# P-MT3620RDB-1-6_WiFi.net
KiCad netlist of a schematic drawn in Altium Designer
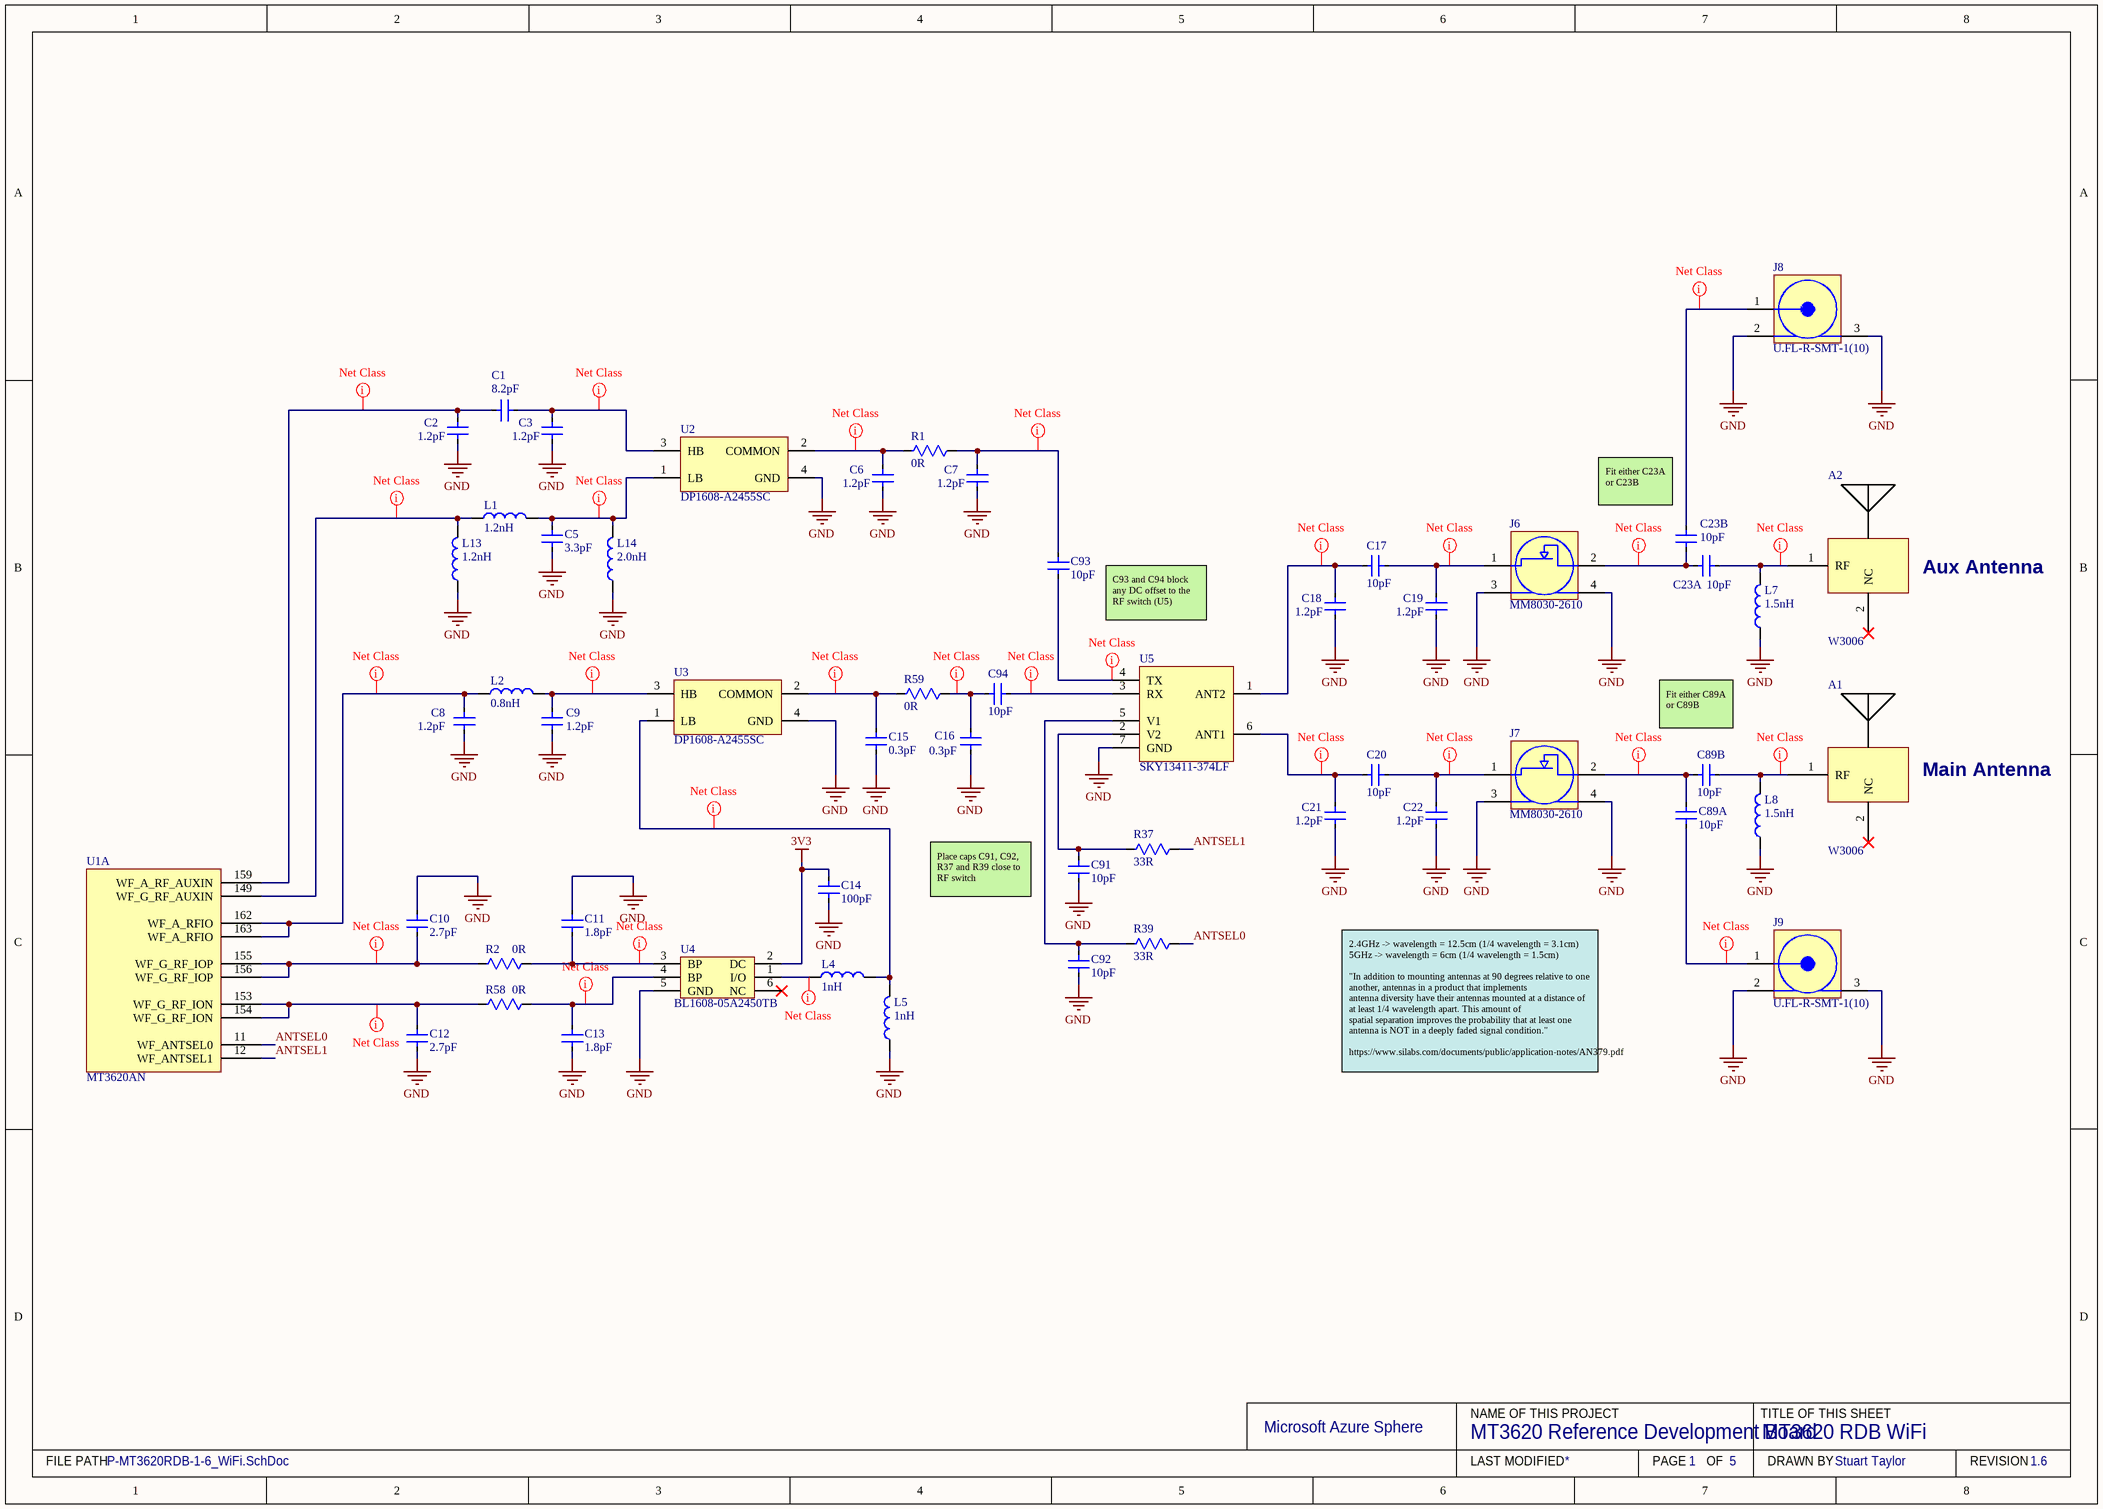
[diagram p0: P-MT3620RDB-1-6_WiFi.SchDoc]

(export (version "E")
  (design (tool "Eeschema 10.0.6"))
  (components
    (comp (ref "A1")
      (value "W3006")
      (footprint "W3006")
      (description "W3006 Chip Antenna")
      (fields (field (name "MANUFACTURER") "Pulse Electronics Corporation"))
      (libsource (lib "Pulse_W3006") (part "W3006"))
    )
    (comp (ref "A2")
      (value "W3006")
      (footprint "W3006")
      (description "W3006 Chip Antenna")
      (fields (field (name "MANUFACTURER") "Pulse Electronics Corporation"))
      (libsource (lib "Pulse_W3006") (part "W3006"))
    )
    (comp (ref "C1")
      (value "8.2pF")
      (footprint "TDK 2010")
      (description "CAP CER 8.2PF 25V NP0 0201")
      (fields
        (field (name "MANUFACTURER") "Murata")
        (field (name "MANUFACTURER PART NUMBER") "GJM0335C1E8R2CB01D")
      )
      (libsource (lib "Murata") (part "GJM0335C1E8R2CB01D"))
    )
    (comp (ref "C2")
      (value "1.2pF")
      (footprint "TDK 2010")
      (description "CAP CER 1.2PF 25V C0G 0201")
      (fields
        (field (name "MANUFACTURER") "TDK Corporation")
        (field (name "MANUFACTURER PART NUMBER") "C0603C0G1E1R2B")
      )
      (libsource (lib "TDK_Capacitor_C_0201") (part "1.2pF 0201 25V"))
    )
    (comp (ref "C3")
      (value "1.2pF")
      (footprint "TDK 2010")
      (description "CAP CER 1.2PF 25V C0G 0201")
      (fields
        (field (name "MANUFACTURER") "TDK Corporation")
        (field (name "MANUFACTURER PART NUMBER") "C0603C0G1E1R2B")
      )
      (libsource (lib "TDK_Capacitor_C_0201") (part "1.2pF 0201 25V"))
    )
    (comp (ref "C5")
      (value "3.3pF")
      (footprint "TDK 2010")
      (description "Cap Ceramic 3.3pF 25V C0G 0.25pF SMD 0201 125C T/R")
      (fields
        (field (name "MANUFACTURER") "TDK")
        (field (name "MANUFACTURER PART NUMBER") "CGA1A2C0G1E3R3C030BA")
      )
      (libsource (lib "TDK_Capacitor_C_0201") (part "3.3pF 0201 25V"))
    )
    (comp (ref "C6")
      (value "1.2pF")
      (footprint "TDK 2010")
      (description "CAP CER 1.2PF 25V C0G 0201")
      (fields
        (field (name "MANUFACTURER") "TDK Corporation")
        (field (name "MANUFACTURER PART NUMBER") "C0603C0G1E1R2B")
      )
      (libsource (lib "TDK_Capacitor_C_0201") (part "1.2pF 0201 25V"))
    )
    (comp (ref "C7")
      (value "1.2pF")
      (footprint "TDK 2010")
      (description "CAP CER 1.2PF 25V C0G 0201")
      (fields
        (field (name "MANUFACTURER") "TDK Corporation")
        (field (name "MANUFACTURER PART NUMBER") "C0603C0G1E1R2B")
      )
      (libsource (lib "TDK_Capacitor_C_0201") (part "1.2pF 0201 25V"))
    )
    (comp (ref "C8")
      (value "1.2pF")
      (footprint "TDK 2010")
      (description "CAP CER 1.2PF 25V C0G 0201")
      (fields
        (field (name "MANUFACTURER") "TDK Corporation")
        (field (name "MANUFACTURER PART NUMBER") "C0603C0G1E1R2B")
      )
      (libsource (lib "TDK_Capacitor_C_0201") (part "1.2pF 0201 25V"))
    )
    (comp (ref "C9")
      (value "1.2pF")
      (footprint "TDK 2010")
      (description "CAP CER 1.2PF 25V C0G 0201")
      (fields
        (field (name "MANUFACTURER") "TDK Corporation")
        (field (name "MANUFACTURER PART NUMBER") "C0603C0G1E1R2B")
      )
      (libsource (lib "TDK_Capacitor_C_0201") (part "1.2pF 0201 25V"))
    )
    (comp (ref "C10")
      (value "2.7pF")
      (footprint "TDK 2010")
      (description "CAP CER 2.7PF 25V C0G 0201")
      (fields (field (name "MANUFACTURER") "TDK") (field (name "MANUFACTURER PART NUMBER") "C0603C0G1E2R7B"))
      (libsource (lib "TDK_Capacitor_C_0201") (part "2.7pF 0201 25V"))
    )
    (comp (ref "C11")
      (value "1.8pF")
      (footprint "TDK 2010")
      (description "CAP CER 1.8PF 25V NP0 0201")
      (fields
        (field (name "MANUFACTURER") "Murata")
        (field (name "MANUFACTURER PART NUMBER") "GJM0335C1E1R8CB01D")
      )
      (libsource (lib "Murata") (part "GJM0335C1E1R8CB01D"))
    )
    (comp (ref "C12")
      (value "2.7pF")
      (footprint "TDK 2010")
      (description "CAP CER 2.7PF 25V C0G 0201")
      (fields (field (name "MANUFACTURER") "TDK") (field (name "MANUFACTURER PART NUMBER") "C0603C0G1E2R7B"))
      (libsource (lib "TDK_Capacitor_C_0201") (part "2.7pF 0201 25V"))
    )
    (comp (ref "C13")
      (value "1.8pF")
      (footprint "TDK 2010")
      (description "CAP CER 1.8PF 25V NP0 0201")
      (fields
        (field (name "MANUFACTURER") "Murata")
        (field (name "MANUFACTURER PART NUMBER") "GJM0335C1E1R8CB01D")
      )
      (libsource (lib "Murata") (part "GJM0335C1E1R8CB01D"))
    )
    (comp (ref "C14")
      (value "100pF")
      (footprint "CAPC1005-EIA0402 0.55MM MED")
      (description "CAP CER 100PF 50V 5% NP0 0402")
      (fields
        (field (name "MANUFACTURER") "TDK Corporation")
        (field (name "MANUFACTURER PART NUMBER") "C1005C0G1H101J050BA")
        (field (name "CAPACITANCE") "100pF")
      )
      (libsource (lib "TDK_Capacitor_C_0402") (part "100pF 0402 C0G, NP0 50V"))
    )
    (comp (ref "C15")
      (value "0.3pF")
      (footprint "TDK 2010")
      (description "CAP CER 0.3PF 25V C0G 0201")
      (fields
        (field (name "MANUFACTURER") "TDK Corporation")
        (field (name "MANUFACTURER PART NUMBER") "C0603C0G1E0R3B")
      )
      (libsource (lib "TDK_Capacitor_C_0201") (part "0.3pF 0201 25V"))
    )
    (comp (ref "C16")
      (value "0.3pF")
      (footprint "TDK 2010")
      (description "CAP CER 0.3PF 25V C0G 0201")
      (fields
        (field (name "MANUFACTURER") "TDK Corporation")
        (field (name "MANUFACTURER PART NUMBER") "C0603C0G1E0R3B")
      )
      (libsource (lib "TDK_Capacitor_C_0201") (part "0.3pF 0201 25V"))
    )
    (comp (ref "C17")
      (value "10pF")
      (footprint "TDK 2010")
      (description "CAP CER 10PF 25V C0G 0201")
      (fields
        (field (name "MANUFACTURER") "TDK Corporation")
        (field (name "MANUFACTURER PART NUMBER") "C0603C0G1E100D030BA")
      )
      (libsource (lib "TDK_Capacitor_C_0201") (part "10pF 0201 25V"))
    )
    (comp (ref "C18")
      (value "1.2pF")
      (footprint "TDK 2010")
      (description "CAP CER 1.2PF 25V C0G 0201")
      (fields
        (field (name "MANUFACTURER") "TDK Corporation")
        (field (name "MANUFACTURER PART NUMBER") "C0603C0G1E1R2B")
      )
      (libsource (lib "TDK_Capacitor_C_0201") (part "1.2pF 0201 25V"))
    )
    (comp (ref "C19")
      (value "1.2pF")
      (footprint "TDK 2010")
      (description "CAP CER 1.2PF 25V C0G 0201")
      (fields
        (field (name "MANUFACTURER") "TDK Corporation")
        (field (name "MANUFACTURER PART NUMBER") "C0603C0G1E1R2B")
      )
      (libsource (lib "TDK_Capacitor_C_0201") (part "1.2pF 0201 25V"))
    )
    (comp (ref "C20")
      (value "10pF")
      (footprint "TDK 2010")
      (description "CAP CER 10PF 25V C0G 0201")
      (fields
        (field (name "MANUFACTURER") "TDK Corporation")
        (field (name "MANUFACTURER PART NUMBER") "C0603C0G1E100D030BA")
      )
      (libsource (lib "TDK_Capacitor_C_0201") (part "10pF 0201 25V"))
    )
    (comp (ref "C21")
      (value "1.2pF")
      (footprint "TDK 2010")
      (description "CAP CER 1.2PF 25V C0G 0201")
      (fields
        (field (name "MANUFACTURER") "TDK Corporation")
        (field (name "MANUFACTURER PART NUMBER") "C0603C0G1E1R2B")
      )
      (libsource (lib "TDK_Capacitor_C_0201") (part "1.2pF 0201 25V"))
    )
    (comp (ref "C22")
      (value "1.2pF")
      (footprint "TDK 2010")
      (description "CAP CER 1.2PF 25V C0G 0201")
      (fields
        (field (name "MANUFACTURER") "TDK Corporation")
        (field (name "MANUFACTURER PART NUMBER") "C0603C0G1E1R2B")
      )
      (libsource (lib "TDK_Capacitor_C_0201") (part "1.2pF 0201 25V"))
    )
    (comp (ref "C23")
      (value "10pF")
      (footprint "CAPC1005-EIA0402 0.55MM MED - THREE WAY")
      (description "CAP CER 10PF 50V NP0 0402 - Three-way pads")
      (fields
        (field (name "MANUFACTURER") "TDK Corporation")
        (field (name "MANUFACTURER PART NUMBER") "C1005C0G1H100D050BA")
        (field (name "CAPACITANCE") "10pF")
      )
      (libsource (lib "TDK_Capacitor_C_0402") (part "10pF 0402 C0G, NP0 50V_1"))
    )
    (comp (ref "C89")
      (value "10pF")
      (footprint "CAPC1005-EIA0402 0.55MM MED - THREE WAY")
      (description "CAP CER 10PF 50V NP0 0402 - Three-way pads")
      (fields
        (field (name "MANUFACTURER") "TDK Corporation")
        (field (name "MANUFACTURER PART NUMBER") "C1005C0G1H100D050BA")
        (field (name "CAPACITANCE") "10pF")
      )
      (libsource (lib "TDK_Capacitor_C_0402") (part "10pF 0402 C0G, NP0 50V_1"))
    )
    (comp (ref "C91")
      (value "10pF")
      (footprint "TDK 2010")
      (description "CAP CER 10PF 25V C0G 0201")
      (fields
        (field (name "MANUFACTURER") "TDK Corporation")
        (field (name "MANUFACTURER PART NUMBER") "C0603C0G1E100D030BA")
      )
      (libsource (lib "TDK_Capacitor_C_0201") (part "10pF 0201 25V"))
    )
    (comp (ref "C92")
      (value "10pF")
      (footprint "TDK 2010")
      (description "CAP CER 10PF 25V C0G 0201")
      (fields
        (field (name "MANUFACTURER") "TDK Corporation")
        (field (name "MANUFACTURER PART NUMBER") "C0603C0G1E100D030BA")
      )
      (libsource (lib "TDK_Capacitor_C_0201") (part "10pF 0201 25V"))
    )
    (comp (ref "C93")
      (value "10pF")
      (footprint "TDK 2010")
      (description "CAP CER 10PF 25V C0G 0201")
      (fields
        (field (name "MANUFACTURER") "TDK Corporation")
        (field (name "MANUFACTURER PART NUMBER") "C0603C0G1E100D030BA")
      )
      (libsource (lib "TDK_Capacitor_C_0201") (part "10pF 0201 25V"))
    )
    (comp (ref "C94")
      (value "10pF")
      (footprint "TDK 2010")
      (description "CAP CER 10PF 25V C0G 0201")
      (fields
        (field (name "MANUFACTURER") "TDK Corporation")
        (field (name "MANUFACTURER PART NUMBER") "C0603C0G1E100D030BA")
      )
      (libsource (lib "TDK_Capacitor_C_0201") (part "10pF 0201 25V"))
    )
    (comp (ref "J6")
      (value "MM8030-2610")
      (footprint "MM8030-2610")
      (description "CONN UMC RECEPT SMD 2x2mm")
      (fields
        (field (name "MANUFACTURER") "Murata Electronics North America")
        (field (name "MANUFACTURER PART NUMBER") "MM8030-2610RK0")
      )
      (libsource (lib "Murata") (part "MM8030-2610"))
    )
    (comp (ref "J7")
      (value "MM8030-2610")
      (footprint "MM8030-2610")
      (description "CONN UMC RECEPT SMD 2x2mm")
      (fields
        (field (name "MANUFACTURER") "Murata Electronics North America")
        (field (name "MANUFACTURER PART NUMBER") "MM8030-2610RK0")
      )
      (libsource (lib "Murata") (part "MM8030-2610"))
    )
    (comp (ref "J8")
      (value "U.FL-R-SMT-1(10)")
      (footprint "U.FL-R-SMT-1(10)")
      (description "CONN UMC JACK STR 50 OHM SMD")
      (fields (field (name "MANUFACTURER") "Hirose Electric (HRS)"))
      (libsource (lib "Hirose") (part "U.FL-R-SMT-1(10)"))
    )
    (comp (ref "J9")
      (value "U.FL-R-SMT-1(10)")
      (footprint "U.FL-R-SMT-1(10)")
      (description "CONN UMC JACK STR 50 OHM SMD")
      (fields (field (name "MANUFACTURER") "Hirose Electric (HRS)"))
      (libsource (lib "Hirose") (part "U.FL-R-SMT-1(10)"))
    )
    (comp (ref "L1")
      (value "1.2nH")
      (footprint "TDK 2010")
      (description "FIXED IND 1.2NH 1A 80 MOHM SMD")
      (fields
        (field (name "MANUFACTURER") "TDK")
        (field (name "MANUFACTURER PART NUMBER") "MHQ0603P1N2CT000")
      )
      (libsource (lib "TDK") (part "1.2nH 0201"))
    )
    (comp (ref "L2")
      (value "0.8nH")
      (footprint "TDK 2010")
      (description "FIXED IND 0.8NH 1A 70 MOHM SMD")
      (fields
        (field (name "MANUFACTURER") "TDK Corporation")
        (field (name "MANUFACTURER PART NUMBER") "MHQ0603P0N8CT000")
      )
      (libsource (lib "TDK") (part "0.8nH 0201"))
    )
    (comp (ref "L4")
      (value "1nH")
      (footprint "TDK 2010")
      (description "FIXED IND 1NH 1A 70 MOHM SMD")
      (fields
        (field (name "MANUFACTURER") "TDK Corporation")
        (field (name "MANUFACTURER PART NUMBER") "MHQ0603P1N0CT000")
      )
      (libsource (lib "TDK") (part "1nH 0201"))
    )
    (comp (ref "L5")
      (value "1nH")
      (footprint "TDK 2010")
      (description "FIXED IND 1NH 1A 70 MOHM SMD")
      (fields
        (field (name "MANUFACTURER") "TDK Corporation")
        (field (name "MANUFACTURER PART NUMBER") "MHQ0603P1N0CT000")
      )
      (libsource (lib "TDK") (part "1nH 0201"))
    )
    (comp (ref "L7")
      (value "1.5nH")
      (footprint "TDK 2010")
      (description "MURATA - LQP03TN1N5B02D - INDUCTOR, 1.5NH, 0.6A, 0.1NH, 15GHZ")
      (fields
        (field (name "MANUFACTURER") "MURATA")
        (field (name "MANUFACTURER PART NUMBER") "LQP03TN1N5B02D")
      )
      (libsource (lib "Murata") (part "LQP03TN1N5B02D"))
    )
    (comp (ref "L8")
      (value "1.5nH")
      (footprint "TDK 2010")
      (description "MURATA - LQP03TN1N5B02D - INDUCTOR, 1.5NH, 0.6A, 0.1NH, 15GHZ")
      (fields
        (field (name "MANUFACTURER") "MURATA")
        (field (name "MANUFACTURER PART NUMBER") "LQP03TN1N5B02D")
      )
      (libsource (lib "Murata") (part "LQP03TN1N5B02D"))
    )
    (comp (ref "L13")
      (value "1.2nH")
      (footprint "TDK 2010")
      (description "FIXED IND 1.2NH 1A 80 MOHM SMD")
      (fields
        (field (name "MANUFACTURER") "TDK")
        (field (name "MANUFACTURER PART NUMBER") "MHQ0603P1N2CT000")
      )
      (libsource (lib "TDK") (part "1.2nH 0201"))
    )
    (comp (ref "L14")
      (value "2.0nH")
      (footprint "TDK 2010")
      (description "FIXED IND 2NH 700MA 120 MOHM SMD")
      (fields
        (field (name "MANUFACTURER") "TDK")
        (field (name "MANUFACTURER PART NUMBER") "MHQ0603P2N0CT000")
      )
      (libsource (lib "TDK") (part "2.0nH 0201"))
    )
    (comp (ref "R1")
      (value "0R")
      (footprint "TDK 2010")
      (description "RES SMD 0.0OHM JUMPER 1/20W 0201")
      (fields
        (field (name "MANUFACTURER") "Panasonic Electronic Components")
        (field (name "MANUFACTURER PART NUMBER") "ERJ-1GN0R00C")
      )
      (libsource (lib "Panasonic_Resistor_ERJ1GN") (part "0R 0201"))
    )
    (comp (ref "R2")
      (value "0R")
      (footprint "TDK 2010")
      (description "RES SMD 0.0OHM JUMPER 1/20W 0201")
      (fields
        (field (name "MANUFACTURER") "Panasonic Electronic Components")
        (field (name "MANUFACTURER PART NUMBER") "ERJ-1GN0R00C")
      )
      (libsource (lib "Panasonic_Resistor_ERJ1GN") (part "0R 0201"))
    )
    (comp (ref "R37")
      (value "33R")
      (footprint "RES 0402 MEDIUM DENSITY")
      (description "RES 33 OHM 1/10W 1% 0402 SMD")
      (fields
        (field (name "MANUFACTURER") "Panasonic Electronic Components")
        (field (name "MANUFACTURER PART NUMBER") "ERJ-2RKF33R0X")
        (field (name "RESISTANCE (OHMS)") "33R")
      )
      (libsource (lib "Panasonic_Resistor_ERJ2R") (part "33R"))
    )
    (comp (ref "R39")
      (value "33R")
      (footprint "RES 0402 MEDIUM DENSITY")
      (description "RES 33 OHM 1/10W 1% 0402 SMD")
      (fields
        (field (name "MANUFACTURER") "Panasonic Electronic Components")
        (field (name "MANUFACTURER PART NUMBER") "ERJ-2RKF33R0X")
        (field (name "RESISTANCE (OHMS)") "33R")
      )
      (libsource (lib "Panasonic_Resistor_ERJ2R") (part "33R"))
    )
    (comp (ref "R58")
      (value "0R")
      (footprint "TDK 2010")
      (description "RES SMD 0.0OHM JUMPER 1/20W 0201")
      (fields
        (field (name "MANUFACTURER") "Panasonic Electronic Components")
        (field (name "MANUFACTURER PART NUMBER") "ERJ-1GN0R00C")
      )
      (libsource (lib "Panasonic_Resistor_ERJ1GN") (part "0R 0201"))
    )
    (comp (ref "R59")
      (value "0R")
      (footprint "TDK 2010")
      (description "RES SMD 0.0OHM JUMPER 1/20W 0201")
      (fields
        (field (name "MANUFACTURER") "Panasonic Electronic Components")
        (field (name "MANUFACTURER PART NUMBER") "ERJ-1GN0R00C")
      )
      (libsource (lib "Panasonic_Resistor_ERJ1GN") (part "0R 0201"))
    )
    (comp (ref "U1")
      (value "MT3620AN")
      (footprint "MT3620_MaskSquaresVias50")
      (libsource (lib "Microsoft") (part "MT3620AN"))
    )
    (comp (ref "U2")
      (value "DP1608-A2455SC")
      (footprint "DP1608-A2455SC")
      (description "Diplexer")
      (libsource (lib "ACX") (part "DP1608-A2455SC"))
    )
    (comp (ref "U3")
      (value "DP1608-A2455SC")
      (footprint "DP1608-A2455SC")
      (description "Diplexer")
      (libsource (lib "ACX") (part "DP1608-A2455SC"))
    )
    (comp (ref "U4")
      (value "BL1608-05A2450TB")
      (footprint "BL1608-05A2450TB")
      (description "Balun")
      (libsource (lib "ACX") (part "BL1608-05A2450TB"))
    )
    (comp (ref "U5")
      (value "SKY13411-374LF")
      (footprint "SKY13411-374LF")
      (description "RF SWITCH")
      (fields (field (name "MANUFACTURER") "Skyworks Solutions Inc."))
      (libsource (lib "Skyworks") (part "SKY13411-374LF"))
    )
  )
  (nets
    (net (code "1") (name "/ANTSEL0") (class "Default")
      (node (ref "R39") (pin "1") (pinfunction "1_1") (pintype "passive"))
      (node (ref "U1") (pin "11") (pinfunction "WF_ANTSEL0_11") (pintype "passive"))
    )
    (net (code "2") (name "/ANTSEL1") (class "Default")
      (node (ref "R37") (pin "1") (pinfunction "1_1") (pintype "passive"))
      (node (ref "U1") (pin "12") (pinfunction "WF_ANTSEL1_12") (pintype "passive"))
    )
    (net (code "3") (name "3V3") (class "Default")
      (node (ref "C14") (pin "2") (pinfunction "2_2") (pintype "passive"))
      (node (ref "U4") (pin "2") (pinfunction "DC_2") (pintype "passive"))
    )
    (net (code "4") (name "GND") (class "Default")
      (node (ref "C10") (pin "2") (pinfunction "2_2") (pintype "passive"))
      (node (ref "C11") (pin "2") (pinfunction "2_2") (pintype "passive"))
      (node (ref "C12") (pin "1") (pinfunction "1_1") (pintype "passive"))
      (node (ref "C13") (pin "1") (pinfunction "1_1") (pintype "passive"))
      (node (ref "C14") (pin "1") (pinfunction "1_1") (pintype "passive"))
      (node (ref "C15") (pin "1") (pinfunction "1_1") (pintype "passive"))
      (node (ref "C16") (pin "1") (pinfunction "1_1") (pintype "passive"))
      (node (ref "C18") (pin "1") (pinfunction "1_1") (pintype "passive"))
      (node (ref "C19") (pin "1") (pinfunction "1_1") (pintype "passive"))
      (node (ref "C2") (pin "1") (pinfunction "1_1") (pintype "passive"))
      (node (ref "C21") (pin "1") (pinfunction "1_1") (pintype "passive"))
      (node (ref "C22") (pin "1") (pinfunction "1_1") (pintype "passive"))
      (node (ref "C3") (pin "1") (pinfunction "1_1") (pintype "passive"))
      (node (ref "C5") (pin "1") (pinfunction "1_1") (pintype "passive"))
      (node (ref "C6") (pin "1") (pinfunction "1_1") (pintype "passive"))
      (node (ref "C7") (pin "1") (pinfunction "1_1") (pintype "passive"))
      (node (ref "C8") (pin "1") (pinfunction "1_1") (pintype "passive"))
      (node (ref "C9") (pin "1") (pinfunction "1_1") (pintype "passive"))
      (node (ref "C91") (pin "1") (pinfunction "1_1") (pintype "passive"))
      (node (ref "C92") (pin "1") (pinfunction "1_1") (pintype "passive"))
      (node (ref "J6") (pin "3") (pinfunction "GND_3") (pintype "passive"))
      (node (ref "J6") (pin "4") (pinfunction "GND_4") (pintype "passive"))
      (node (ref "J7") (pin "3") (pinfunction "GND_3") (pintype "passive"))
      (node (ref "J7") (pin "4") (pinfunction "GND_4") (pintype "passive"))
      (node (ref "J8") (pin "2") (pinfunction "GND_2") (pintype "passive"))
      (node (ref "J8") (pin "3") (pinfunction "GND_3") (pintype "passive"))
      (node (ref "J9") (pin "2") (pinfunction "GND_2") (pintype "passive"))
      (node (ref "J9") (pin "3") (pinfunction "GND_3") (pintype "passive"))
      (node (ref "L13") (pin "1") (pinfunction "1_1") (pintype "passive"))
      (node (ref "L14") (pin "1") (pinfunction "1_1") (pintype "passive"))
      (node (ref "L5") (pin "1") (pinfunction "1_1") (pintype "passive"))
      (node (ref "L7") (pin "1") (pinfunction "1_1") (pintype "passive"))
      (node (ref "L8") (pin "1") (pinfunction "1_1") (pintype "passive"))
      (node (ref "U2") (pin "4") (pinfunction "GND_4") (pintype "passive"))
      (node (ref "U3") (pin "4") (pinfunction "GND_4") (pintype "passive"))
      (node (ref "U4") (pin "5") (pinfunction "GND_5") (pintype "passive"))
      (node (ref "U5") (pin "7") (pinfunction "GND_7") (pintype "passive"))
    )
    (net (code "5") (name "Net-(A1-RF)") (class "Default")
      (node (ref "A1") (pin "1") (pinfunction "RF_1") (pintype "passive"))
      (node (ref "C89") (pin "3") (pinfunction "3_3") (pintype "passive"))
      (node (ref "L8") (pin "2") (pinfunction "2_2") (pintype "passive"))
    )
    (net (code "6") (name "Net-(A2-RF)") (class "Default")
      (node (ref "A2") (pin "1") (pinfunction "RF_1") (pintype "passive"))
      (node (ref "C23") (pin "2") (pinfunction "2_2") (pintype "passive"))
      (node (ref "L7") (pin "2") (pinfunction "2_2") (pintype "passive"))
    )
    (net (code "7") (name "Net-(C7-Pad2)") (class "Default")
      (node (ref "C7") (pin "2") (pinfunction "2_2") (pintype "passive"))
      (node (ref "C93") (pin "2") (pinfunction "2_2") (pintype "passive"))
      (node (ref "R1") (pin "1") (pinfunction "1_1") (pintype "passive"))
    )
    (net (code "8") (name "Net-(C8-Pad2)") (class "Default")
      (node (ref "C8") (pin "2") (pinfunction "2_2") (pintype "passive"))
      (node (ref "L2") (pin "1") (pinfunction "1_1") (pintype "passive"))
      (node (ref "U1") (pin "162") (pinfunction "WF_A_RFIO_162") (pintype "passive"))
      (node (ref "U1") (pin "163") (pinfunction "WF_A_RFIO_163") (pintype "passive"))
    )
    (net (code "9") (name "Net-(C10-Pad1)") (class "Default")
      (node (ref "C10") (pin "1") (pinfunction "1_1") (pintype "passive"))
      (node (ref "R2") (pin "2") (pinfunction "2_2") (pintype "passive"))
      (node (ref "U1") (pin "155") (pinfunction "WF_G_RF_IOP_155") (pintype "passive"))
      (node (ref "U1") (pin "156") (pinfunction "WF_G_RF_IOP_156") (pintype "passive"))
    )
    (net (code "10") (name "Net-(C11-Pad1)") (class "Default")
      (node (ref "C11") (pin "1") (pinfunction "1_1") (pintype "passive"))
      (node (ref "R2") (pin "1") (pinfunction "1_1") (pintype "passive"))
      (node (ref "U4") (pin "3") (pinfunction "BP_3") (pintype "passive"))
    )
    (net (code "11") (name "Net-(C12-Pad2)") (class "Default")
      (node (ref "C12") (pin "2") (pinfunction "2_2") (pintype "passive"))
      (node (ref "R58") (pin "2") (pinfunction "2_2") (pintype "passive"))
      (node (ref "U1") (pin "153") (pinfunction "WF_G_RF_ION_153") (pintype "passive"))
      (node (ref "U1") (pin "154") (pinfunction "WF_G_RF_ION_154") (pintype "passive"))
    )
    (net (code "12") (name "Net-(C13-Pad2)") (class "Default")
      (node (ref "C13") (pin "2") (pinfunction "2_2") (pintype "passive"))
      (node (ref "R58") (pin "1") (pinfunction "1_1") (pintype "passive"))
      (node (ref "U4") (pin "4") (pinfunction "BP_4") (pintype "passive"))
    )
    (net (code "13") (name "Net-(C16-Pad2)") (class "Default")
      (node (ref "C16") (pin "2") (pinfunction "2_2") (pintype "passive"))
      (node (ref "C94") (pin "2") (pinfunction "2_2") (pintype "passive"))
      (node (ref "R59") (pin "1") (pinfunction "1_1") (pintype "passive"))
    )
    (net (code "14") (name "Net-(J6-IN)") (class "Default")
      (node (ref "C17") (pin "2") (pinfunction "2_2") (pintype "passive"))
      (node (ref "C19") (pin "2") (pinfunction "2_2") (pintype "passive"))
      (node (ref "J6") (pin "1") (pinfunction "IN_1") (pintype "passive"))
    )
    (net (code "15") (name "Net-(J6-OUT)") (class "Default")
      (node (ref "C23") (pin "1") (pinfunction "1_1") (pintype "passive"))
      (node (ref "J6") (pin "2") (pinfunction "OUT_2") (pintype "passive"))
    )
    (net (code "16") (name "Net-(J7-IN)") (class "Default")
      (node (ref "C20") (pin "2") (pinfunction "2_2") (pintype "passive"))
      (node (ref "C22") (pin "2") (pinfunction "2_2") (pintype "passive"))
      (node (ref "J7") (pin "1") (pinfunction "IN_1") (pintype "passive"))
    )
    (net (code "17") (name "Net-(J7-OUT)") (class "Default")
      (node (ref "C89") (pin "1") (pinfunction "1_1") (pintype "passive"))
      (node (ref "J7") (pin "2") (pinfunction "OUT_2") (pintype "passive"))
    )
    (net (code "18") (name "Net-(J8-IN)") (class "Default")
      (node (ref "C23") (pin "3") (pinfunction "3_3") (pintype "passive"))
      (node (ref "J8") (pin "1") (pinfunction "IN_1") (pintype "passive"))
    )
    (net (code "19") (name "Net-(J9-IN)") (class "Default")
      (node (ref "C89") (pin "2") (pinfunction "2_2") (pintype "passive"))
      (node (ref "J9") (pin "1") (pinfunction "IN_1") (pintype "passive"))
    )
    (net (code "20") (name "Net-(U1A-WF_A_RF_AUXIN)") (class "Default")
      (node (ref "C1") (pin "1") (pinfunction "1_1") (pintype "passive"))
      (node (ref "C2") (pin "2") (pinfunction "2_2") (pintype "passive"))
      (node (ref "U1") (pin "159") (pinfunction "WF_A_RF_AUXIN_159") (pintype "passive"))
    )
    (net (code "21") (name "Net-(U1A-WF_G_RF_AUXIN)") (class "Default")
      (node (ref "L1") (pin "1") (pinfunction "1_1") (pintype "passive"))
      (node (ref "L13") (pin "2") (pinfunction "2_2") (pintype "passive"))
      (node (ref "U1") (pin "149") (pinfunction "WF_G_RF_AUXIN_149") (pintype "passive"))
    )
    (net (code "22") (name "Net-(U2-COMMON)") (class "Default")
      (node (ref "C6") (pin "2") (pinfunction "2_2") (pintype "passive"))
      (node (ref "R1") (pin "2") (pinfunction "2_2") (pintype "passive"))
      (node (ref "U2") (pin "2") (pinfunction "COMMON_2") (pintype "passive"))
    )
    (net (code "23") (name "Net-(U2-HB)") (class "Default")
      (node (ref "C1") (pin "2") (pinfunction "2_2") (pintype "passive"))
      (node (ref "C3") (pin "2") (pinfunction "2_2") (pintype "passive"))
      (node (ref "U2") (pin "3") (pinfunction "HB_3") (pintype "passive"))
    )
    (net (code "24") (name "Net-(U2-LB)") (class "Default")
      (node (ref "C5") (pin "2") (pinfunction "2_2") (pintype "passive"))
      (node (ref "L1") (pin "2") (pinfunction "2_2") (pintype "passive"))
      (node (ref "L14") (pin "2") (pinfunction "2_2") (pintype "passive"))
      (node (ref "U2") (pin "1") (pinfunction "LB_1") (pintype "passive"))
    )
    (net (code "25") (name "Net-(U3-COMMON)") (class "Default")
      (node (ref "C15") (pin "2") (pinfunction "2_2") (pintype "passive"))
      (node (ref "R59") (pin "2") (pinfunction "2_2") (pintype "passive"))
      (node (ref "U3") (pin "2") (pinfunction "COMMON_2") (pintype "passive"))
    )
    (net (code "26") (name "Net-(U3-HB)") (class "Default")
      (node (ref "C9") (pin "2") (pinfunction "2_2") (pintype "passive"))
      (node (ref "L2") (pin "2") (pinfunction "2_2") (pintype "passive"))
      (node (ref "U3") (pin "3") (pinfunction "HB_3") (pintype "passive"))
    )
    (net (code "27") (name "Net-(U3-LB)") (class "Default")
      (node (ref "L4") (pin "2") (pinfunction "2_2") (pintype "passive"))
      (node (ref "L5") (pin "2") (pinfunction "2_2") (pintype "passive"))
      (node (ref "U3") (pin "1") (pinfunction "LB_1") (pintype "passive"))
    )
    (net (code "28") (name "Net-(U4-I{slash}O)") (class "Default")
      (node (ref "L4") (pin "1") (pinfunction "1_1") (pintype "passive"))
      (node (ref "U4") (pin "1") (pinfunction "I/O_1") (pintype "passive"))
    )
    (net (code "29") (name "Net-(U5-ANT1)") (class "Default")
      (node (ref "C20") (pin "1") (pinfunction "1_1") (pintype "passive"))
      (node (ref "C21") (pin "2") (pinfunction "2_2") (pintype "passive"))
      (node (ref "U5") (pin "6") (pinfunction "ANT1_6") (pintype "passive"))
    )
    (net (code "30") (name "Net-(U5-ANT2)") (class "Default")
      (node (ref "C17") (pin "1") (pinfunction "1_1") (pintype "passive"))
      (node (ref "C18") (pin "2") (pinfunction "2_2") (pintype "passive"))
      (node (ref "U5") (pin "1") (pinfunction "ANT2_1") (pintype "passive"))
    )
    (net (code "31") (name "Net-(U5-RX)") (class "Default")
      (node (ref "C94") (pin "1") (pinfunction "1_1") (pintype "passive"))
      (node (ref "U5") (pin "3") (pinfunction "RX_3") (pintype "passive"))
    )
    (net (code "32") (name "Net-(U5-TX)") (class "Default")
      (node (ref "C93") (pin "1") (pinfunction "1_1") (pintype "passive"))
      (node (ref "U5") (pin "4") (pinfunction "TX_4") (pintype "passive"))
    )
    (net (code "33") (name "Net-(U5-V1)") (class "Default")
      (node (ref "C92") (pin "2") (pinfunction "2_2") (pintype "passive"))
      (node (ref "R39") (pin "2") (pinfunction "2_2") (pintype "passive"))
      (node (ref "U5") (pin "5") (pinfunction "V1_5") (pintype "passive"))
    )
    (net (code "34") (name "Net-(U5-V2)") (class "Default")
      (node (ref "C91") (pin "2") (pinfunction "2_2") (pintype "passive"))
      (node (ref "R37") (pin "2") (pinfunction "2_2") (pintype "passive"))
      (node (ref "U5") (pin "2") (pinfunction "V2_2") (pintype "passive"))
    )
    (net (code "35") (name "unconnected-(A1-NC-Pad2)") (class "Default")
      (node (ref "A1") (pin "2") (pinfunction "NC_2") (pintype "passive+no_connect"))
    )
    (net (code "36") (name "unconnected-(A2-NC-Pad2)") (class "Default")
      (node (ref "A2") (pin "2") (pinfunction "NC_2") (pintype "passive+no_connect"))
    )
    (net (code "37") (name "unconnected-(U4-NC-Pad6)") (class "Default")
      (node (ref "U4") (pin "6") (pinfunction "NC_6") (pintype "passive+no_connect"))
    )
  )
)
